# Thermocouples.net
KiCad netlist of a schematic drawn in Altium Designer
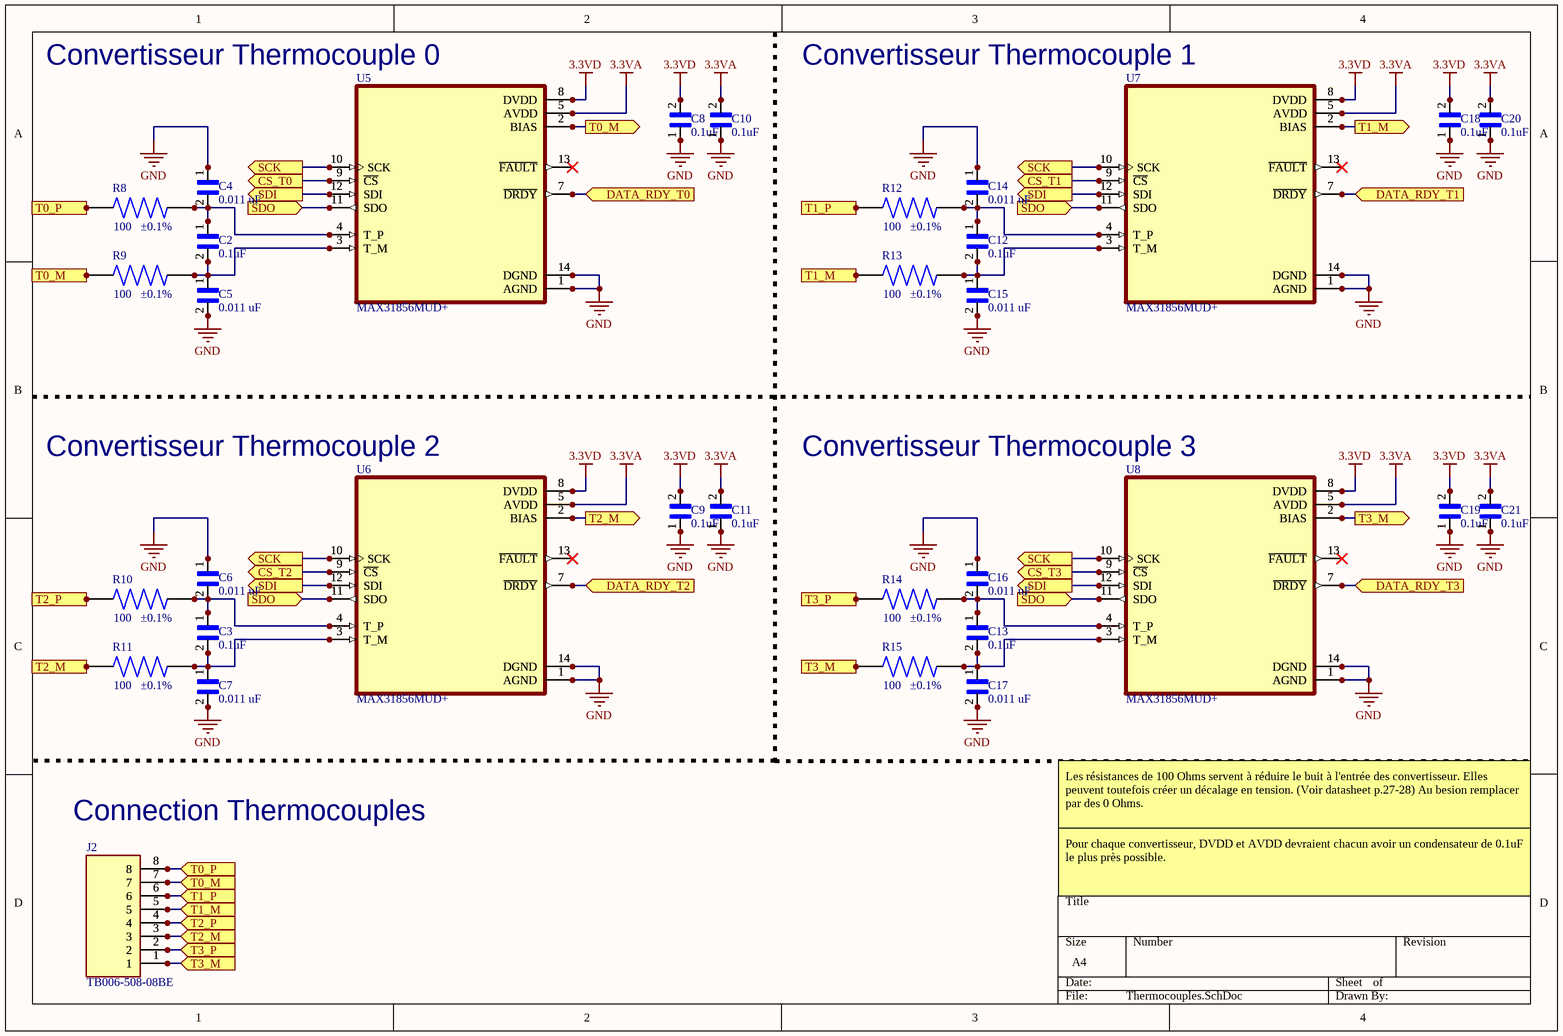
[diagram p0: Thermocouples.SchDoc]

(export (version "E")
  (design (tool "Eeschema 10.0.6"))
  (components
    (comp (ref "C2")
      (value "0.1uF")
      (footprint "C3216C0G1H104J160AA")
      (fields (field (name "Comment") "C3216C0G1H104J160AA"))
      (libsource (lib "") (part "C3216C0G1H104J160AA_1"))
    )
    (comp (ref "C3")
      (value "0.1uF")
      (footprint "C3216C0G1H104J160AA")
      (fields (field (name "Comment") "C3216C0G1H104J160AA"))
      (libsource (lib "") (part "C3216C0G1H104J160AA_1"))
    )
    (comp (ref "C4")
      (value "0.011 uF")
      (footprint "GRM3195C1H113JA01D")
      (fields (field (name "Comment") "GRM3195C1H113JA01D"))
      (libsource (lib "GRM3195C1H113JA01D") (part "GRM3195C1H113JA01D"))
    )
    (comp (ref "C5")
      (value "0.011 uF")
      (footprint "GRM3195C1H113JA01D")
      (fields (field (name "Comment") "GRM3195C1H113JA01D"))
      (libsource (lib "GRM3195C1H113JA01D") (part "GRM3195C1H113JA01D"))
    )
    (comp (ref "C6")
      (value "0.011 uF")
      (footprint "GRM3195C1H113JA01D")
      (fields (field (name "Comment") "GRM3195C1H113JA01D"))
      (libsource (lib "GRM3195C1H113JA01D") (part "GRM3195C1H113JA01D"))
    )
    (comp (ref "C7")
      (value "0.011 uF")
      (footprint "GRM3195C1H113JA01D")
      (fields (field (name "Comment") "GRM3195C1H113JA01D"))
      (libsource (lib "GRM3195C1H113JA01D") (part "GRM3195C1H113JA01D"))
    )
    (comp (ref "C8")
      (value "0.1uF")
      (footprint "C3216C0G1H104J160AA")
      (fields (field (name "Comment") "C3216C0G1H104J160AA"))
      (libsource (lib "C3216C0G1H104J160AA") (part "C3216C0G1H104J160AA"))
    )
    (comp (ref "C9")
      (value "0.1uF")
      (footprint "C3216C0G1H104J160AA")
      (fields (field (name "Comment") "C3216C0G1H104J160AA"))
      (libsource (lib "C3216C0G1H104J160AA") (part "C3216C0G1H104J160AA"))
    )
    (comp (ref "C10")
      (value "0.1uF")
      (footprint "C3216C0G1H104J160AA")
      (fields (field (name "Comment") "C3216C0G1H104J160AA"))
      (libsource (lib "C3216C0G1H104J160AA") (part "C3216C0G1H104J160AA"))
    )
    (comp (ref "C11")
      (value "0.1uF")
      (footprint "C3216C0G1H104J160AA")
      (fields (field (name "Comment") "C3216C0G1H104J160AA"))
      (libsource (lib "C3216C0G1H104J160AA") (part "C3216C0G1H104J160AA"))
    )
    (comp (ref "C12")
      (value "0.1uF")
      (footprint "C3216C0G1H104J160AA")
      (fields (field (name "Comment") "C3216C0G1H104J160AA"))
      (libsource (lib "") (part "C3216C0G1H104J160AA_1"))
    )
    (comp (ref "C13")
      (value "0.1uF")
      (footprint "C3216C0G1H104J160AA")
      (fields (field (name "Comment") "C3216C0G1H104J160AA"))
      (libsource (lib "") (part "C3216C0G1H104J160AA_1"))
    )
    (comp (ref "C14")
      (value "0.011 uF")
      (footprint "GRM3195C1H113JA01D")
      (fields (field (name "Comment") "GRM3195C1H113JA01D"))
      (libsource (lib "GRM3195C1H113JA01D") (part "GRM3195C1H113JA01D"))
    )
    (comp (ref "C15")
      (value "0.011 uF")
      (footprint "GRM3195C1H113JA01D")
      (fields (field (name "Comment") "GRM3195C1H113JA01D"))
      (libsource (lib "GRM3195C1H113JA01D") (part "GRM3195C1H113JA01D"))
    )
    (comp (ref "C16")
      (value "0.011 uF")
      (footprint "GRM3195C1H113JA01D")
      (fields (field (name "Comment") "GRM3195C1H113JA01D"))
      (libsource (lib "GRM3195C1H113JA01D") (part "GRM3195C1H113JA01D"))
    )
    (comp (ref "C17")
      (value "0.011 uF")
      (footprint "GRM3195C1H113JA01D")
      (fields (field (name "Comment") "GRM3195C1H113JA01D"))
      (libsource (lib "GRM3195C1H113JA01D") (part "GRM3195C1H113JA01D"))
    )
    (comp (ref "C18")
      (value "0.1uF")
      (footprint "C3216C0G1H104J160AA")
      (fields (field (name "Comment") "C3216C0G1H104J160AA"))
      (libsource (lib "C3216C0G1H104J160AA") (part "C3216C0G1H104J160AA"))
    )
    (comp (ref "C19")
      (value "0.1uF")
      (footprint "C3216C0G1H104J160AA")
      (fields (field (name "Comment") "C3216C0G1H104J160AA"))
      (libsource (lib "C3216C0G1H104J160AA") (part "C3216C0G1H104J160AA"))
    )
    (comp (ref "C20")
      (value "0.1uF")
      (footprint "C3216C0G1H104J160AA")
      (fields (field (name "Comment") "C3216C0G1H104J160AA"))
      (libsource (lib "C3216C0G1H104J160AA") (part "C3216C0G1H104J160AA"))
    )
    (comp (ref "C21")
      (value "0.1uF")
      (footprint "C3216C0G1H104J160AA")
      (fields (field (name "Comment") "C3216C0G1H104J160AA"))
      (libsource (lib "C3216C0G1H104J160AA") (part "C3216C0G1H104J160AA"))
    )
    (comp (ref "J2")
      (value "TB006-508-08BE")
      (footprint "TB006-508-08BE")
      (libsource (lib "TB006-508-08BE") (part "TB006-508-08BE"))
    )
    (comp (ref "R8")
      (value "100")
      (footprint "RNCS1206BKE100R")
      (description "Res Thin Film 1206 100 Ohm 0.1% 0.125W(1/8W)")
      (fields (field (name "TOLERANCE") "±0.1%") (field (name "Comment") "RNCS1206BKE100R"))
      (libsource (lib "RNCS1206BKE100R") (part "RNCS1206BKE100R"))
    )
    (comp (ref "R9")
      (value "100")
      (footprint "RNCS1206BKE100R")
      (description "Res Thin Film 1206 100 Ohm 0.1% 0.125W(1/8W)")
      (fields (field (name "TOLERANCE") "±0.1%") (field (name "Comment") "RNCS1206BKE100R"))
      (libsource (lib "RNCS1206BKE100R") (part "RNCS1206BKE100R"))
    )
    (comp (ref "R10")
      (value "100")
      (footprint "RNCS1206BKE100R")
      (description "Res Thin Film 1206 100 Ohm 0.1% 0.125W(1/8W)")
      (fields (field (name "TOLERANCE") "±0.1%") (field (name "Comment") "RNCS1206BKE100R"))
      (libsource (lib "RNCS1206BKE100R") (part "RNCS1206BKE100R"))
    )
    (comp (ref "R11")
      (value "100")
      (footprint "RNCS1206BKE100R")
      (description "Res Thin Film 1206 100 Ohm 0.1% 0.125W(1/8W)")
      (fields (field (name "TOLERANCE") "±0.1%") (field (name "Comment") "RNCS1206BKE100R"))
      (libsource (lib "RNCS1206BKE100R") (part "RNCS1206BKE100R"))
    )
    (comp (ref "R12")
      (value "100")
      (footprint "RNCS1206BKE100R")
      (description "Res Thin Film 1206 100 Ohm 0.1% 0.125W(1/8W)")
      (fields (field (name "TOLERANCE") "±0.1%") (field (name "Comment") "RNCS1206BKE100R"))
      (libsource (lib "RNCS1206BKE100R") (part "RNCS1206BKE100R"))
    )
    (comp (ref "R13")
      (value "100")
      (footprint "RNCS1206BKE100R")
      (description "Res Thin Film 1206 100 Ohm 0.1% 0.125W(1/8W)")
      (fields (field (name "TOLERANCE") "±0.1%") (field (name "Comment") "RNCS1206BKE100R"))
      (libsource (lib "RNCS1206BKE100R") (part "RNCS1206BKE100R"))
    )
    (comp (ref "R14")
      (value "100")
      (footprint "RNCS1206BKE100R")
      (description "Res Thin Film 1206 100 Ohm 0.1% 0.125W(1/8W)")
      (fields (field (name "TOLERANCE") "±0.1%") (field (name "Comment") "RNCS1206BKE100R"))
      (libsource (lib "RNCS1206BKE100R") (part "RNCS1206BKE100R"))
    )
    (comp (ref "R15")
      (value "100")
      (footprint "RNCS1206BKE100R")
      (description "Res Thin Film 1206 100 Ohm 0.1% 0.125W(1/8W)")
      (fields (field (name "TOLERANCE") "±0.1%") (field (name "Comment") "RNCS1206BKE100R"))
      (libsource (lib "RNCS1206BKE100R") (part "RNCS1206BKE100R"))
    )
    (comp (ref "U5")
      (value "MAX31856MUD+")
      (footprint "PCBComponent_1")
      (libsource (lib "MAX31856MUD") (part "MAX31856MUD+"))
    )
    (comp (ref "U6")
      (value "MAX31856MUD+")
      (footprint "PCBComponent_1")
      (libsource (lib "MAX31856MUD") (part "MAX31856MUD+"))
    )
    (comp (ref "U7")
      (value "MAX31856MUD+")
      (footprint "PCBComponent_1")
      (libsource (lib "MAX31856MUD") (part "MAX31856MUD+"))
    )
    (comp (ref "U8")
      (value "MAX31856MUD+")
      (footprint "PCBComponent_1")
      (libsource (lib "MAX31856MUD") (part "MAX31856MUD+"))
    )
  )
  (nets
    (net (code "1") (name "/CS_T0") (class "Default")
      (node (ref "U5") (pin "9") (pinfunction "~{CS}_9") (pintype "input"))
    )
    (net (code "2") (name "/CS_T1") (class "Default")
      (node (ref "U7") (pin "9") (pinfunction "~{CS}_9") (pintype "input"))
    )
    (net (code "3") (name "/CS_T2") (class "Default")
      (node (ref "U6") (pin "9") (pinfunction "~{CS}_9") (pintype "input"))
    )
    (net (code "4") (name "/CS_T3") (class "Default")
      (node (ref "U8") (pin "9") (pinfunction "~{CS}_9") (pintype "input"))
    )
    (net (code "5") (name "/DATA_RDY_T0") (class "Default")
      (node (ref "U5") (pin "7") (pinfunction "~{DRDY}_7") (pintype "output"))
    )
    (net (code "6") (name "/DATA_RDY_T1") (class "Default")
      (node (ref "U7") (pin "7") (pinfunction "~{DRDY}_7") (pintype "output"))
    )
    (net (code "7") (name "/DATA_RDY_T2") (class "Default")
      (node (ref "U6") (pin "7") (pinfunction "~{DRDY}_7") (pintype "output"))
    )
    (net (code "8") (name "/DATA_RDY_T3") (class "Default")
      (node (ref "U8") (pin "7") (pinfunction "~{DRDY}_7") (pintype "output"))
    )
    (net (code "9") (name "/SCK") (class "Default")
      (node (ref "U5") (pin "10") (pinfunction "SCK_10") (pintype "input"))
      (node (ref "U6") (pin "10") (pinfunction "SCK_10") (pintype "input"))
      (node (ref "U7") (pin "10") (pinfunction "SCK_10") (pintype "input"))
      (node (ref "U8") (pin "10") (pinfunction "SCK_10") (pintype "input"))
    )
    (net (code "10") (name "/SDI") (class "Default")
      (node (ref "U5") (pin "12") (pinfunction "SDI_12") (pintype "input"))
      (node (ref "U6") (pin "12") (pinfunction "SDI_12") (pintype "input"))
      (node (ref "U7") (pin "12") (pinfunction "SDI_12") (pintype "input"))
      (node (ref "U8") (pin "12") (pinfunction "SDI_12") (pintype "input"))
    )
    (net (code "11") (name "/SDO") (class "Default")
      (node (ref "U5") (pin "11") (pinfunction "SDO_11") (pintype "output"))
      (node (ref "U6") (pin "11") (pinfunction "SDO_11") (pintype "output"))
      (node (ref "U7") (pin "11") (pinfunction "SDO_11") (pintype "output"))
      (node (ref "U8") (pin "11") (pinfunction "SDO_11") (pintype "output"))
    )
    (net (code "12") (name "/T0_M") (class "Default")
      (node (ref "J2") (pin "7") (pinfunction "7_7") (pintype "passive"))
      (node (ref "R9") (pin "1") (pinfunction "1_1") (pintype "passive"))
      (node (ref "U5") (pin "2") (pinfunction "BIAS_2") (pintype "power_in"))
    )
    (net (code "13") (name "/T0_P") (class "Default")
      (node (ref "J2") (pin "8") (pinfunction "8_8") (pintype "passive"))
      (node (ref "R8") (pin "1") (pinfunction "1_1") (pintype "passive"))
    )
    (net (code "14") (name "/T1_M") (class "Default")
      (node (ref "J2") (pin "5") (pinfunction "5_5") (pintype "passive"))
      (node (ref "R13") (pin "1") (pinfunction "1_1") (pintype "passive"))
      (node (ref "U7") (pin "2") (pinfunction "BIAS_2") (pintype "power_in"))
    )
    (net (code "15") (name "/T1_P") (class "Default")
      (node (ref "J2") (pin "6") (pinfunction "6_6") (pintype "passive"))
      (node (ref "R12") (pin "1") (pinfunction "1_1") (pintype "passive"))
    )
    (net (code "16") (name "/T2_M") (class "Default")
      (node (ref "J2") (pin "3") (pinfunction "3_3") (pintype "passive"))
      (node (ref "R11") (pin "1") (pinfunction "1_1") (pintype "passive"))
      (node (ref "U6") (pin "2") (pinfunction "BIAS_2") (pintype "power_in"))
    )
    (net (code "17") (name "/T2_P") (class "Default")
      (node (ref "J2") (pin "4") (pinfunction "4_4") (pintype "passive"))
      (node (ref "R10") (pin "1") (pinfunction "1_1") (pintype "passive"))
    )
    (net (code "18") (name "/T3_M") (class "Default")
      (node (ref "J2") (pin "1") (pinfunction "1_1") (pintype "passive"))
      (node (ref "R15") (pin "1") (pinfunction "1_1") (pintype "passive"))
      (node (ref "U8") (pin "2") (pinfunction "BIAS_2") (pintype "power_in"))
    )
    (net (code "19") (name "/T3_P") (class "Default")
      (node (ref "J2") (pin "2") (pinfunction "2_2") (pintype "passive"))
      (node (ref "R14") (pin "1") (pinfunction "1_1") (pintype "passive"))
    )
    (net (code "20") (name "3.3VA") (class "Default")
      (node (ref "C10") (pin "2") (pinfunction "2_2") (pintype "passive"))
      (node (ref "C11") (pin "2") (pinfunction "2_2") (pintype "passive"))
      (node (ref "C20") (pin "2") (pinfunction "2_2") (pintype "passive"))
      (node (ref "C21") (pin "2") (pinfunction "2_2") (pintype "passive"))
      (node (ref "U5") (pin "5") (pinfunction "AVDD_5") (pintype "power_in"))
      (node (ref "U6") (pin "5") (pinfunction "AVDD_5") (pintype "power_in"))
      (node (ref "U7") (pin "5") (pinfunction "AVDD_5") (pintype "power_in"))
      (node (ref "U8") (pin "5") (pinfunction "AVDD_5") (pintype "power_in"))
    )
    (net (code "21") (name "3.3VD") (class "Default")
      (node (ref "C18") (pin "2") (pinfunction "2_2") (pintype "passive"))
      (node (ref "C19") (pin "2") (pinfunction "2_2") (pintype "passive"))
      (node (ref "C8") (pin "2") (pinfunction "2_2") (pintype "passive"))
      (node (ref "C9") (pin "2") (pinfunction "2_2") (pintype "passive"))
      (node (ref "U5") (pin "8") (pinfunction "DVDD_8") (pintype "power_in"))
      (node (ref "U6") (pin "8") (pinfunction "DVDD_8") (pintype "power_in"))
      (node (ref "U7") (pin "8") (pinfunction "DVDD_8") (pintype "power_in"))
      (node (ref "U8") (pin "8") (pinfunction "DVDD_8") (pintype "power_in"))
    )
    (net (code "22") (name "GND") (class "Default")
      (node (ref "C10") (pin "1") (pinfunction "1_1") (pintype "passive"))
      (node (ref "C11") (pin "1") (pinfunction "1_1") (pintype "passive"))
      (node (ref "C14") (pin "1") (pinfunction "1_1") (pintype "passive"))
      (node (ref "C15") (pin "2") (pinfunction "2_2") (pintype "passive"))
      (node (ref "C16") (pin "1") (pinfunction "1_1") (pintype "passive"))
      (node (ref "C17") (pin "2") (pinfunction "2_2") (pintype "passive"))
      (node (ref "C18") (pin "1") (pinfunction "1_1") (pintype "passive"))
      (node (ref "C19") (pin "1") (pinfunction "1_1") (pintype "passive"))
      (node (ref "C20") (pin "1") (pinfunction "1_1") (pintype "passive"))
      (node (ref "C21") (pin "1") (pinfunction "1_1") (pintype "passive"))
      (node (ref "C4") (pin "1") (pinfunction "1_1") (pintype "passive"))
      (node (ref "C5") (pin "2") (pinfunction "2_2") (pintype "passive"))
      (node (ref "C6") (pin "1") (pinfunction "1_1") (pintype "passive"))
      (node (ref "C7") (pin "2") (pinfunction "2_2") (pintype "passive"))
      (node (ref "C8") (pin "1") (pinfunction "1_1") (pintype "passive"))
      (node (ref "C9") (pin "1") (pinfunction "1_1") (pintype "passive"))
      (node (ref "U5") (pin "1") (pinfunction "AGND_1") (pintype "power_in"))
      (node (ref "U5") (pin "14") (pinfunction "DGND_14") (pintype "power_in"))
      (node (ref "U6") (pin "1") (pinfunction "AGND_1") (pintype "power_in"))
      (node (ref "U6") (pin "14") (pinfunction "DGND_14") (pintype "power_in"))
      (node (ref "U7") (pin "1") (pinfunction "AGND_1") (pintype "power_in"))
      (node (ref "U7") (pin "14") (pinfunction "DGND_14") (pintype "power_in"))
      (node (ref "U8") (pin "1") (pinfunction "AGND_1") (pintype "power_in"))
      (node (ref "U8") (pin "14") (pinfunction "DGND_14") (pintype "power_in"))
    )
    (net (code "23") (name "Net-(U5-T_M)") (class "Default")
      (node (ref "C2") (pin "2") (pinfunction "2_2") (pintype "passive"))
      (node (ref "C5") (pin "1") (pinfunction "1_1") (pintype "passive"))
      (node (ref "R9") (pin "2") (pinfunction "2_2") (pintype "passive"))
      (node (ref "U5") (pin "3") (pinfunction "T_M_3") (pintype "input"))
    )
    (net (code "24") (name "Net-(U5-T_P)") (class "Default")
      (node (ref "C2") (pin "1") (pinfunction "1_1") (pintype "passive"))
      (node (ref "C4") (pin "2") (pinfunction "2_2") (pintype "passive"))
      (node (ref "R8") (pin "2") (pinfunction "2_2") (pintype "passive"))
      (node (ref "U5") (pin "4") (pinfunction "T_P_4") (pintype "input"))
    )
    (net (code "25") (name "Net-(U6-T_M)") (class "Default")
      (node (ref "C3") (pin "2") (pinfunction "2_2") (pintype "passive"))
      (node (ref "C7") (pin "1") (pinfunction "1_1") (pintype "passive"))
      (node (ref "R11") (pin "2") (pinfunction "2_2") (pintype "passive"))
      (node (ref "U6") (pin "3") (pinfunction "T_M_3") (pintype "input"))
    )
    (net (code "26") (name "Net-(U6-T_P)") (class "Default")
      (node (ref "C3") (pin "1") (pinfunction "1_1") (pintype "passive"))
      (node (ref "C6") (pin "2") (pinfunction "2_2") (pintype "passive"))
      (node (ref "R10") (pin "2") (pinfunction "2_2") (pintype "passive"))
      (node (ref "U6") (pin "4") (pinfunction "T_P_4") (pintype "input"))
    )
    (net (code "27") (name "Net-(U7-T_M)") (class "Default")
      (node (ref "C12") (pin "2") (pinfunction "2_2") (pintype "passive"))
      (node (ref "C15") (pin "1") (pinfunction "1_1") (pintype "passive"))
      (node (ref "R13") (pin "2") (pinfunction "2_2") (pintype "passive"))
      (node (ref "U7") (pin "3") (pinfunction "T_M_3") (pintype "input"))
    )
    (net (code "28") (name "Net-(U7-T_P)") (class "Default")
      (node (ref "C12") (pin "1") (pinfunction "1_1") (pintype "passive"))
      (node (ref "C14") (pin "2") (pinfunction "2_2") (pintype "passive"))
      (node (ref "R12") (pin "2") (pinfunction "2_2") (pintype "passive"))
      (node (ref "U7") (pin "4") (pinfunction "T_P_4") (pintype "input"))
    )
    (net (code "29") (name "Net-(U8-T_M)") (class "Default")
      (node (ref "C13") (pin "2") (pinfunction "2_2") (pintype "passive"))
      (node (ref "C17") (pin "1") (pinfunction "1_1") (pintype "passive"))
      (node (ref "R15") (pin "2") (pinfunction "2_2") (pintype "passive"))
      (node (ref "U8") (pin "3") (pinfunction "T_M_3") (pintype "input"))
    )
    (net (code "30") (name "Net-(U8-T_P)") (class "Default")
      (node (ref "C13") (pin "1") (pinfunction "1_1") (pintype "passive"))
      (node (ref "C16") (pin "2") (pinfunction "2_2") (pintype "passive"))
      (node (ref "R14") (pin "2") (pinfunction "2_2") (pintype "passive"))
      (node (ref "U8") (pin "4") (pinfunction "T_P_4") (pintype "input"))
    )
    (net (code "31") (name "unconnected-(U5-~{FAULT}-Pad13)") (class "Default")
      (node (ref "U5") (pin "13") (pinfunction "~{FAULT}_13") (pintype "output+no_connect"))
    )
    (net (code "32") (name "unconnected-(U6-~{FAULT}-Pad13)") (class "Default")
      (node (ref "U6") (pin "13") (pinfunction "~{FAULT}_13") (pintype "output+no_connect"))
    )
    (net (code "33") (name "unconnected-(U7-~{FAULT}-Pad13)") (class "Default")
      (node (ref "U7") (pin "13") (pinfunction "~{FAULT}_13") (pintype "output+no_connect"))
    )
    (net (code "34") (name "unconnected-(U8-~{FAULT}-Pad13)") (class "Default")
      (node (ref "U8") (pin "13") (pinfunction "~{FAULT}_13") (pintype "output+no_connect"))
    )
  )
)
